# 32u4_denemesi.net
KiCad netlist of a schematic drawn in EAGLE
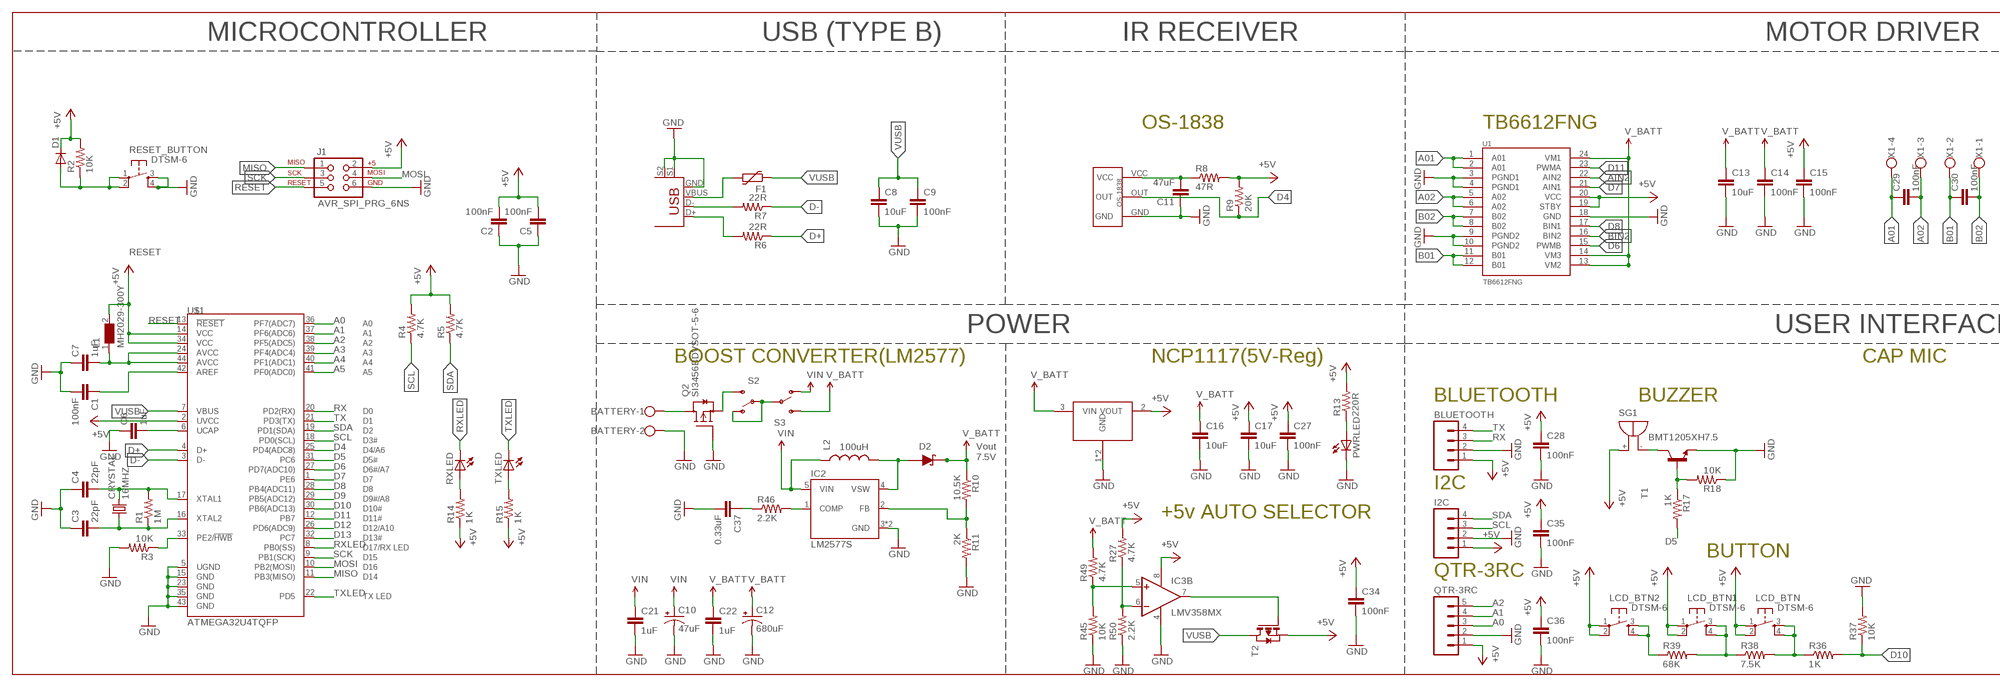
[diagram p0: schematic, sheet 1, part 1 of 2]
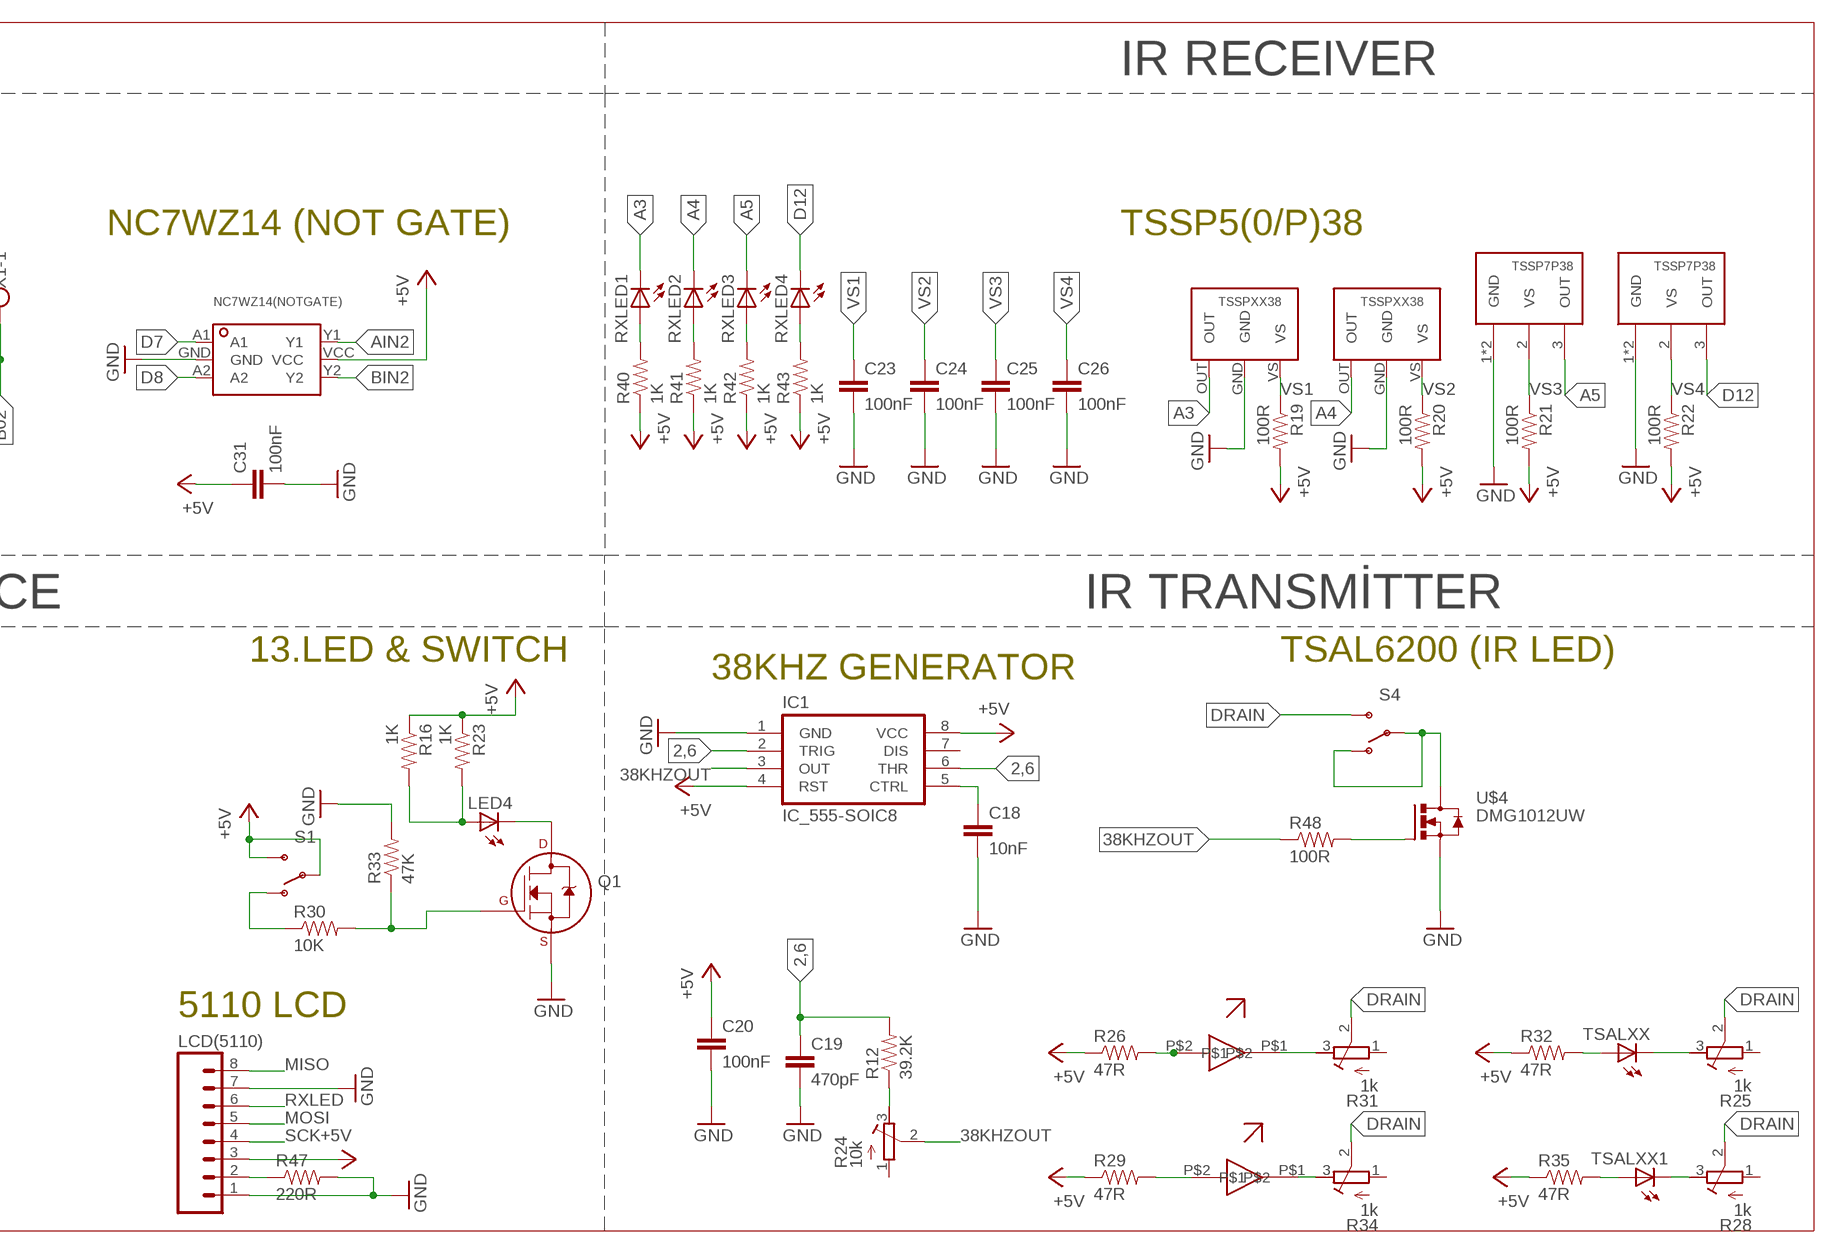
[diagram p1: schematic, sheet 1, part 2 of 2]

(export (version "E")
  (design (tool "Eeschema 10.0.6"))
  (components
    (comp (ref "BATTERY")
      (value "W237-102")
      (footprint "eagle-import:W237-102")
      (fields (field (name "MPN") "237-102"))
      (libsource (lib "eagle-import") (part "W237-102"))
    )
    (comp (ref "BLUETOOTH")
      (value "M04PTH")
      (footprint "eagle-import:1X04")
      (libsource (lib "eagle-import") (part "M04PTH"))
    )
    (comp (ref "C1")
      (value "100nF")
      (footprint "eagle-import:1206")
      (libsource (lib "eagle-import") (part "CAP1206"))
    )
    (comp (ref "C2")
      (value "100nF")
      (footprint "eagle-import:1206")
      (libsource (lib "eagle-import") (part "CAP1206"))
    )
    (comp (ref "C3")
      (value "22pF")
      (footprint "eagle-import:1206")
      (libsource (lib "eagle-import") (part "CAP1206"))
    )
    (comp (ref "C4")
      (value "22pF")
      (footprint "eagle-import:1206")
      (libsource (lib "eagle-import") (part "CAP1206"))
    )
    (comp (ref "C5")
      (value "100nF")
      (footprint "eagle-import:1206")
      (libsource (lib "eagle-import") (part "CAP1206"))
    )
    (comp (ref "C6")
      (value "1uF")
      (footprint "eagle-import:1206")
      (libsource (lib "eagle-import") (part "CAP1206"))
    )
    (comp (ref "C7")
      (value "1uF")
      (footprint "eagle-import:1206")
      (libsource (lib "eagle-import") (part "CAP1206"))
    )
    (comp (ref "C8")
      (value "10uF")
      (footprint "eagle-import:1206")
      (libsource (lib "eagle-import") (part "CAP1206"))
    )
    (comp (ref "C9")
      (value "100nF")
      (footprint "eagle-import:1206")
      (libsource (lib "eagle-import") (part "CAP1206"))
    )
    (comp (ref "C10")
      (value "47uF")
      (footprint "eagle-import:NIPPON_F80")
      (libsource (lib "eagle-import") (part "CAP_POLF80"))
    )
    (comp (ref "C11")
      (value "47uF")
      (footprint "eagle-import:1206")
      (libsource (lib "eagle-import") (part "CAP1206"))
    )
    (comp (ref "C12")
      (value "680uF")
      (footprint "eagle-import:PANASONIC_G")
      (libsource (lib "eagle-import") (part "CAP_POLG"))
    )
    (comp (ref "C13")
      (value "10uF")
      (footprint "eagle-import:1206")
      (libsource (lib "eagle-import") (part "CAP1206"))
    )
    (comp (ref "C14")
      (value "100nF")
      (footprint "eagle-import:1206")
      (libsource (lib "eagle-import") (part "CAP1206"))
    )
    (comp (ref "C15")
      (value "100nF")
      (footprint "eagle-import:1206")
      (libsource (lib "eagle-import") (part "CAP1206"))
    )
    (comp (ref "C16")
      (value "10uF")
      (footprint "eagle-import:1206")
      (libsource (lib "eagle-import") (part "CAP1206"))
    )
    (comp (ref "C17")
      (value "10uF")
      (footprint "eagle-import:1206")
      (libsource (lib "eagle-import") (part "CAP1206"))
    )
    (comp (ref "C18")
      (value "10nF")
      (footprint "eagle-import:1206")
      (libsource (lib "eagle-import") (part "CAP1206"))
    )
    (comp (ref "C19")
      (value "470pF")
      (footprint "eagle-import:1206")
      (libsource (lib "eagle-import") (part "CAP1206"))
    )
    (comp (ref "C20")
      (value "100nF")
      (footprint "eagle-import:1206")
      (libsource (lib "eagle-import") (part "CAP1206"))
    )
    (comp (ref "C21")
      (value "1uF")
      (footprint "eagle-import:1206")
      (libsource (lib "eagle-import") (part "CAP1206"))
    )
    (comp (ref "C22")
      (value "1uF")
      (footprint "eagle-import:1206")
      (libsource (lib "eagle-import") (part "CAP1206"))
    )
    (comp (ref "C23")
      (value "100nF")
      (footprint "eagle-import:1206")
      (libsource (lib "eagle-import") (part "CAP1206"))
    )
    (comp (ref "C24")
      (value "100nF")
      (footprint "eagle-import:1206")
      (libsource (lib "eagle-import") (part "CAP1206"))
    )
    (comp (ref "C25")
      (value "100nF")
      (footprint "eagle-import:1206")
      (libsource (lib "eagle-import") (part "CAP1206"))
    )
    (comp (ref "C26")
      (value "100nF")
      (footprint "eagle-import:1206")
      (libsource (lib "eagle-import") (part "CAP1206"))
    )
    (comp (ref "C27")
      (value "100nF")
      (footprint "eagle-import:1206")
      (libsource (lib "eagle-import") (part "CAP1206"))
    )
    (comp (ref "C28")
      (value "100nF")
      (footprint "eagle-import:1206")
      (libsource (lib "eagle-import") (part "CAP1206"))
    )
    (comp (ref "C29")
      (value "100nF")
      (footprint "eagle-import:1206")
      (libsource (lib "eagle-import") (part "CAP1206"))
    )
    (comp (ref "C30")
      (value "100nF")
      (footprint "eagle-import:1206")
      (libsource (lib "eagle-import") (part "CAP1206"))
    )
    (comp (ref "C31")
      (value "100nF")
      (footprint "eagle-import:1206")
      (libsource (lib "eagle-import") (part "CAP1206"))
    )
    (comp (ref "C34")
      (value "100nF")
      (footprint "eagle-import:1206")
      (libsource (lib "eagle-import") (part "CAP1206"))
    )
    (comp (ref "C35")
      (value "100nF")
      (footprint "eagle-import:1206")
      (libsource (lib "eagle-import") (part "CAP1206"))
    )
    (comp (ref "C36")
      (value "100nF")
      (footprint "eagle-import:1206")
      (libsource (lib "eagle-import") (part "CAP1206"))
    )
    (comp (ref "C37")
      (value "0.33uF")
      (footprint "eagle-import:1206")
      (libsource (lib "eagle-import") (part "CAP1206"))
    )
    (comp (ref "CRYSTAL")
      (value "16MHZ")
      (footprint "eagle-import:CRYSTAL-SMD-5X3")
      (libsource (lib "eagle-import") (part "CRYSTAL5X3"))
    )
    (comp (ref "D1")
      (value "DIODE-MINIMELF")
      (footprint "eagle-import:MINIMELF")
      (libsource (lib "eagle-import") (part "DIODE-MINIMELF"))
    )
    (comp (ref "D2")
      (value "D_SCHOTTKYA")
      (footprint "eagle-import:SMA")
      (libsource (lib "eagle-import") (part "D_SCHOTTKYA"))
    )
    (comp (ref "F1")
      (value "FUSE_PTC-0805")
      (footprint "eagle-import:PTC0805")
      (libsource (lib "eagle-import") (part "FUSE_PTC-0805"))
    )
    (comp (ref "I2C")
      (value "M04PTH")
      (footprint "eagle-import:1X04")
      (libsource (lib "eagle-import") (part "M04PTH"))
    )
    (comp (ref "IC1")
      (value "IC_555-SOIC8")
      (footprint "eagle-import:SOIC-8")
      (libsource (lib "eagle-import") (part "IC_555-SOIC8"))
    )
    (comp (ref "IC2")
      (value "LM2577S")
      (footprint "eagle-import:TO263-5")
      (libsource (lib "eagle-import") (part "LM2577S"))
    )
    (comp (ref "IC3")
      (value "LMV358MX")
      (footprint "eagle-import:SO08")
      (libsource (lib "eagle-import") (part "LMV358?MX"))
    )
    (comp (ref "J1")
      (value "AVR_SPI_PRG_6NS")
      (footprint "eagle-import:2X3-NS")
      (libsource (lib "eagle-import") (part "AVR_SPI_PRG_6NS"))
    )
    (comp (ref "L1")
      (value "MH2029-300Y")
      (footprint "eagle-import:0805")
      (libsource (lib "eagle-import") (part "WE-CBF_0805"))
    )
    (comp (ref "L2")
      (value "INDUCTORPWR")
      (footprint "eagle-import:CDRH125")
      (libsource (lib "eagle-import") (part "INDUCTORPWR"))
    )
    (comp (ref "LCD(5110)")
      (value "M081X08")
      (footprint "eagle-import:1X08")
      (libsource (lib "eagle-import") (part "M081X08"))
    )
    (comp (ref "LCD_BTN")
      (value "DTSM-6")
      (footprint "eagle-import:DTSM-6")
      (libsource (lib "eagle-import") (part "DTSM-6"))
    )
    (comp (ref "LCD_BTN1")
      (value "DTSM-6")
      (footprint "eagle-import:DTSM-6")
      (libsource (lib "eagle-import") (part "DTSM-6"))
    )
    (comp (ref "LCD_BTN2")
      (value "DTSM-6")
      (footprint "eagle-import:DTSM-6")
      (libsource (lib "eagle-import") (part "DTSM-6"))
    )
    (comp (ref "LED4")
      (value "LEDCHIPLED_0805")
      (footprint "eagle-import:CHIPLED_0805")
      (libsource (lib "eagle-import") (part "LEDCHIPLED_0805"))
    )
    (comp (ref "PWRLED")
      (value "LEDCHIPLED_0805")
      (footprint "eagle-import:CHIPLED_0805")
      (libsource (lib "eagle-import") (part "LEDCHIPLED_0805"))
    )
    (comp (ref "Q1")
      (value "2N7000_SOT23")
      (footprint "eagle-import:SOT-23")
      (libsource (lib "eagle-import") (part "2N700_SOT230"))
    )
    (comp (ref "Q2")
      (value "SI3456BDVSOT-5-6")
      (footprint "eagle-import:SOT23-6")
      (libsource (lib "eagle-import") (part "SI3456BDVSOT-5-6"))
    )
    (comp (ref "QTR-3RC")
      (value "M05PTH")
      (footprint "eagle-import:1X05")
      (libsource (lib "eagle-import") (part "M05PTH"))
    )
    (comp (ref "R1")
      (value "1M")
      (footprint "eagle-import:0805")
      (libsource (lib "eagle-import") (part "RESISTOR0805-RES"))
    )
    (comp (ref "R2")
      (value "10K")
      (footprint "eagle-import:0805")
      (libsource (lib "eagle-import") (part "RESISTOR0805-RES"))
    )
    (comp (ref "R3")
      (value "10K")
      (footprint "eagle-import:0805")
      (libsource (lib "eagle-import") (part "RESISTOR0805-RES"))
    )
    (comp (ref "R4")
      (value "4.7K")
      (footprint "eagle-import:0805")
      (libsource (lib "eagle-import") (part "RESISTOR0805-RES"))
    )
    (comp (ref "R5")
      (value "4.7K")
      (footprint "eagle-import:0805")
      (libsource (lib "eagle-import") (part "RESISTOR0805-RES"))
    )
    (comp (ref "R6")
      (value "22R")
      (footprint "eagle-import:0805")
      (libsource (lib "eagle-import") (part "RESISTOR0805-RES"))
    )
    (comp (ref "R7")
      (value "22R")
      (footprint "eagle-import:0805")
      (libsource (lib "eagle-import") (part "RESISTOR0805-RES"))
    )
    (comp (ref "R8")
      (value "47R")
      (footprint "eagle-import:0805")
      (libsource (lib "eagle-import") (part "RESISTOR0805-RES"))
    )
    (comp (ref "R9")
      (value "20K")
      (footprint "eagle-import:0805")
      (libsource (lib "eagle-import") (part "RESISTOR0805-RES"))
    )
    (comp (ref "R10")
      (value "10.5K")
      (footprint "eagle-import:0805")
      (libsource (lib "eagle-import") (part "RESISTOR0805-RES"))
    )
    (comp (ref "R11")
      (value "2K")
      (footprint "eagle-import:0805")
      (libsource (lib "eagle-import") (part "RESISTOR0805-RES"))
    )
    (comp (ref "R12")
      (value "39.2K")
      (footprint "eagle-import:0805")
      (libsource (lib "eagle-import") (part "RESISTOR0805-RES"))
    )
    (comp (ref "R13")
      (value "220R")
      (footprint "eagle-import:0805")
      (libsource (lib "eagle-import") (part "RESISTOR0805-RES"))
    )
    (comp (ref "R14")
      (value "1K")
      (footprint "eagle-import:0805")
      (libsource (lib "eagle-import") (part "RESISTOR0805-RES"))
    )
    (comp (ref "R15")
      (value "1K")
      (footprint "eagle-import:0805")
      (libsource (lib "eagle-import") (part "RESISTOR0805-RES"))
    )
    (comp (ref "R16")
      (value "1K")
      (footprint "eagle-import:0805")
      (libsource (lib "eagle-import") (part "RESISTOR0805-RES"))
    )
    (comp (ref "R17")
      (value "1K")
      (footprint "eagle-import:0805")
      (libsource (lib "eagle-import") (part "RESISTOR0805-RES"))
    )
    (comp (ref "R18")
      (value "10K")
      (footprint "eagle-import:0805")
      (libsource (lib "eagle-import") (part "RESISTOR0805-RES"))
    )
    (comp (ref "R19")
      (value "100R")
      (footprint "eagle-import:0805")
      (libsource (lib "eagle-import") (part "RESISTOR0805-RES"))
    )
    (comp (ref "R20")
      (value "100R")
      (footprint "eagle-import:0805")
      (libsource (lib "eagle-import") (part "RESISTOR0805-RES"))
    )
    (comp (ref "R21")
      (value "100R")
      (footprint "eagle-import:0805")
      (libsource (lib "eagle-import") (part "RESISTOR0805-RES"))
    )
    (comp (ref "R22")
      (value "100R")
      (footprint "eagle-import:0805")
      (libsource (lib "eagle-import") (part "RESISTOR0805-RES"))
    )
    (comp (ref "R23")
      (value "1K")
      (footprint "eagle-import:0805")
      (libsource (lib "eagle-import") (part "RESISTOR0805-RES"))
    )
    (comp (ref "R24")
      (value "10k")
      (footprint "eagle-import:RTRIM3296W")
      (libsource (lib "eagle-import") (part "R-TRIMM3296W"))
    )
    (comp (ref "R25")
      (value "1k")
      (footprint "eagle-import:RTRIM3296W")
      (libsource (lib "eagle-import") (part "R-TRIMM3296W"))
    )
    (comp (ref "R26")
      (value "47R")
      (footprint "eagle-import:0805")
      (libsource (lib "eagle-import") (part "RESISTOR0805-RES"))
    )
    (comp (ref "R27")
      (value "4.7K")
      (footprint "eagle-import:0805")
      (libsource (lib "eagle-import") (part "RESISTOR0805-RES"))
    )
    (comp (ref "R28")
      (value "1k")
      (footprint "eagle-import:RTRIM3296W")
      (libsource (lib "eagle-import") (part "R-TRIMM3296W"))
    )
    (comp (ref "R29")
      (value "47R")
      (footprint "eagle-import:0805")
      (libsource (lib "eagle-import") (part "RESISTOR0805-RES"))
    )
    (comp (ref "R30")
      (value "10K")
      (footprint "eagle-import:0805")
      (libsource (lib "eagle-import") (part "RESISTOR0805-RES"))
    )
    (comp (ref "R31")
      (value "1k")
      (footprint "eagle-import:RTRIM3296W")
      (libsource (lib "eagle-import") (part "R-TRIMM3296W"))
    )
    (comp (ref "R32")
      (value "47R")
      (footprint "eagle-import:0805")
      (libsource (lib "eagle-import") (part "RESISTOR0805-RES"))
    )
    (comp (ref "R33")
      (value "47K")
      (footprint "eagle-import:0805")
      (libsource (lib "eagle-import") (part "RESISTOR0805-RES"))
    )
    (comp (ref "R34")
      (value "1k")
      (footprint "eagle-import:RTRIM3296W")
      (libsource (lib "eagle-import") (part "R-TRIMM3296W"))
    )
    (comp (ref "R35")
      (value "47R")
      (footprint "eagle-import:0805")
      (libsource (lib "eagle-import") (part "RESISTOR0805-RES"))
    )
    (comp (ref "R36")
      (value "1K")
      (footprint "eagle-import:0805")
      (libsource (lib "eagle-import") (part "RESISTOR0805-RES"))
    )
    (comp (ref "R37")
      (value "10K")
      (footprint "eagle-import:0805")
      (libsource (lib "eagle-import") (part "RESISTOR0805-RES"))
    )
    (comp (ref "R38")
      (value "7.5K")
      (footprint "eagle-import:0805")
      (libsource (lib "eagle-import") (part "RESISTOR0805-RES"))
    )
    (comp (ref "R39")
      (value "68K")
      (footprint "eagle-import:0805")
      (libsource (lib "eagle-import") (part "RESISTOR0805-RES"))
    )
    (comp (ref "R40")
      (value "1K")
      (footprint "eagle-import:0805")
      (libsource (lib "eagle-import") (part "RESISTOR0805-RES"))
    )
    (comp (ref "R41")
      (value "1K")
      (footprint "eagle-import:0805")
      (libsource (lib "eagle-import") (part "RESISTOR0805-RES"))
    )
    (comp (ref "R42")
      (value "1K")
      (footprint "eagle-import:0805")
      (libsource (lib "eagle-import") (part "RESISTOR0805-RES"))
    )
    (comp (ref "R43")
      (value "1K")
      (footprint "eagle-import:0805")
      (libsource (lib "eagle-import") (part "RESISTOR0805-RES"))
    )
    (comp (ref "R45")
      (value "10K")
      (footprint "eagle-import:0805")
      (libsource (lib "eagle-import") (part "RESISTOR0805-RES"))
    )
    (comp (ref "R46")
      (value "2.2K")
      (footprint "eagle-import:0805")
      (libsource (lib "eagle-import") (part "RESISTOR0805-RES"))
    )
    (comp (ref "R47")
      (value "220R")
      (footprint "eagle-import:0805")
      (libsource (lib "eagle-import") (part "RESISTOR0805-RES"))
    )
    (comp (ref "R48")
      (value "100R")
      (footprint "eagle-import:0805")
      (libsource (lib "eagle-import") (part "RESISTOR0805-RES"))
    )
    (comp (ref "R49")
      (value "4.7K")
      (footprint "eagle-import:0805")
      (libsource (lib "eagle-import") (part "RESISTOR0805-RES"))
    )
    (comp (ref "R50")
      (value "2.2K")
      (footprint "eagle-import:0805")
      (libsource (lib "eagle-import") (part "RESISTOR0805-RES"))
    )
    (comp (ref "RESET_BUTTON")
      (value "DTSM-6")
      (footprint "eagle-import:DTSM-6")
      (libsource (lib "eagle-import") (part "DTSM-6"))
    )
    (comp (ref "RXLED")
      (value "LEDCHIPLED_0805")
      (footprint "eagle-import:CHIPLED_0805")
      (libsource (lib "eagle-import") (part "LEDCHIPLED_0805"))
    )
    (comp (ref "RXLED1")
      (value "LEDCHIPLED_0805")
      (footprint "eagle-import:CHIPLED_0805")
      (libsource (lib "eagle-import") (part "LEDCHIPLED_0805"))
    )
    (comp (ref "RXLED2")
      (value "LEDCHIPLED_0805")
      (footprint "eagle-import:CHIPLED_0805")
      (libsource (lib "eagle-import") (part "LEDCHIPLED_0805"))
    )
    (comp (ref "RXLED3")
      (value "LEDCHIPLED_0805")
      (footprint "eagle-import:CHIPLED_0805")
      (libsource (lib "eagle-import") (part "LEDCHIPLED_0805"))
    )
    (comp (ref "RXLED4")
      (value "LEDCHIPLED_0805")
      (footprint "eagle-import:CHIPLED_0805")
      (libsource (lib "eagle-import") (part "LEDCHIPLED_0805"))
    )
    (comp (ref "S1")
      (value "SWITCH-SPDTPTH")
      (footprint "eagle-import:SWITCH-SPDT")
      (libsource (lib "eagle-import") (part "SWITCH-SPDTPTH"))
    )
    (comp (ref "S2")
      (value "SWITCH-SPDTPTH")
      (footprint "eagle-import:SWITCH-SPDT")
      (libsource (lib "eagle-import") (part "SWITCH-SPDTPTH"))
    )
    (comp (ref "S3")
      (value "SWITCH-SPDTPTH")
      (footprint "eagle-import:SWITCH-SPDT")
      (libsource (lib "eagle-import") (part "SWITCH-SPDTPTH"))
    )
    (comp (ref "S4")
      (value "SWITCH-SPDTPTH")
      (footprint "eagle-import:SWITCH-SPDT")
      (libsource (lib "eagle-import") (part "SWITCH-SPDTPTH"))
    )
    (comp (ref "SG1")
      (value "BMT1205XH7.5")
      (footprint "eagle-import:BMT1205XH7.5")
      (libsource (lib "eagle-import") (part "BMT1205XH7.5"))
    )
    (comp (ref "T1")
      (value "MMBT2222ALT1-NPN-SOT23-BEC")
      (footprint "eagle-import:SOT23-BEC")
      (libsource (lib "eagle-import") (part "-NPN-SOT23-BECMMBT2222ALT1"))
    )
    (comp (ref "T2")
      (value "PMOSSOT23")
      (footprint "eagle-import:SOT-23")
      (libsource (lib "eagle-import") (part "PMOSSOT23"))
    )
    (comp (ref "TSALXX")
      (value "LED5MM")
      (footprint "eagle-import:LED5MM")
      (libsource (lib "eagle-import") (part "LED5MM"))
    )
    (comp (ref "TSALXX1")
      (value "LED5MM")
      (footprint "eagle-import:LED5MM")
      (libsource (lib "eagle-import") (part "LED5MM"))
    )
    (comp (ref "TXLED")
      (value "LEDCHIPLED_0805")
      (footprint "eagle-import:CHIPLED_0805")
      (libsource (lib "eagle-import") (part "LEDCHIPLED_0805"))
    )
    (comp (ref "U$1")
      (value "ATMEGA32U4TQFP")
      (footprint "eagle-import:SPARKFUN-DIGITALIC_TQFP44")
      (libsource (lib "eagle-import") (part "ATMEGA32U4TQFP"))
    )
    (comp (ref "U$2")
      (value "USB+SHIELD")
      (footprint "eagle-import:USB-B-PTH")
      (libsource (lib "eagle-import") (part "USB+SHIELD"))
    )
    (comp (ref "U$3")
      (value "OS-1838")
      (footprint "eagle-import:OS-1838")
      (libsource (lib "eagle-import") (part "OS-1838"))
    )
    (comp (ref "U$4")
      (value "DMG1012UW")
      (footprint "eagle-import:SOT323")
      (libsource (lib "eagle-import") (part "DMG1012UW"))
    )
    (comp (ref "U$5")
      (value "NCP1117")
      (footprint "eagle-import:SOT223")
      (libsource (lib "eagle-import") (part "NCP1117"))
    )
    (comp (ref "U$6")
      (value "TSSP7P38")
      (footprint "eagle-import:TSSP7P38")
      (libsource (lib "eagle-import") (part "TSSP7P38"))
    )
    (comp (ref "U$7")
      (value "TSSP7P38")
      (footprint "eagle-import:TSSP7P38")
      (libsource (lib "eagle-import") (part "TSSP7P38"))
    )
    (comp (ref "U$8")
      (value "TSSPXX38")
      (footprint "eagle-import:TSSPXX38")
      (libsource (lib "eagle-import") (part "TSSPXX38"))
    )
    (comp (ref "U$9")
      (value "TSSPXX38")
      (footprint "eagle-import:TSSPXX38")
      (libsource (lib "eagle-import") (part "TSSPXX38"))
    )
    (comp (ref "U$10")
      (value "NC7WZ14(NOTGATE)")
      (footprint "eagle-import:SC-70-6")
      (libsource (lib "eagle-import") (part "NC7WZ14(NOTGATE)"))
    )
    (comp (ref "U$11")
      (value "IRLED")
      (footprint "eagle-import:IRLED")
      (libsource (lib "eagle-import") (part "IRLED"))
    )
    (comp (ref "U$12")
      (value "IRLED")
      (footprint "eagle-import:IRLED")
      (libsource (lib "eagle-import") (part "IRLED"))
    )
    (comp (ref "U1")
      (value "TB6612FNG")
      (footprint "eagle-import:SSOP24")
      (libsource (lib "eagle-import") (part "TB6621FNG"))
    )
    (comp (ref "X1")
      (value "W237-4")
      (footprint "eagle-import:W237-4")
      (libsource (lib "eagle-import") (part "W237-4"))
    )
  )
  (nets
    (net (code "1") (name "+5V") (class "Default")
      (node (ref "BLUETOOTH") (pin "1") (pinfunction "1_1") (pintype "passive"))
      (node (ref "C15") (pin "1") (pinfunction "1_1") (pintype "passive"))
      (node (ref "C17") (pin "1") (pinfunction "1_1") (pintype "passive"))
      (node (ref "C2") (pin "2") (pinfunction "2_2") (pintype "passive"))
      (node (ref "C20") (pin "1") (pinfunction "1_1") (pintype "passive"))
      (node (ref "C27") (pin "1") (pinfunction "1_1") (pintype "passive"))
      (node (ref "C28") (pin "1") (pinfunction "1_1") (pintype "passive"))
      (node (ref "C31") (pin "1") (pinfunction "1_1") (pintype "passive"))
      (node (ref "C34") (pin "1") (pinfunction "1_1") (pintype "passive"))
      (node (ref "C35") (pin "1") (pinfunction "1_1") (pintype "passive"))
      (node (ref "C36") (pin "1") (pinfunction "1_1") (pintype "passive"))
      (node (ref "C5") (pin "2") (pinfunction "2_2") (pintype "passive"))
      (node (ref "D1") (pin "C") (pinfunction "C_C") (pintype "passive"))
      (node (ref "I2C") (pin "1") (pinfunction "1_1") (pintype "passive"))
      (node (ref "IC1") (pin "4") (pinfunction "RST_4") (pintype "input"))
      (node (ref "IC1") (pin "8") (pinfunction "VCC_8") (pintype "power_in"))
      (node (ref "IC3") (pin "8") (pinfunction "V+_8") (pintype "power_in"))
      (node (ref "J1") (pin "2") (pinfunction "2_2") (pintype "passive"))
      (node (ref "L1") (pin "2") (pinfunction "2_2") (pintype "passive"))
      (node (ref "LCD(5110)") (pin "3") (pinfunction "3_3") (pintype "passive"))
      (node (ref "LCD_BTN") (pin "1") (pinfunction "1_1") (pintype "passive"))
      (node (ref "LCD_BTN") (pin "2") (pinfunction "2_2") (pintype "passive"))
      (node (ref "LCD_BTN1") (pin "1") (pinfunction "1_1") (pintype "passive"))
      (node (ref "LCD_BTN1") (pin "2") (pinfunction "2_2") (pintype "passive"))
      (node (ref "LCD_BTN2") (pin "1") (pinfunction "1_1") (pintype "passive"))
      (node (ref "LCD_BTN2") (pin "2") (pinfunction "2_2") (pintype "passive"))
      (node (ref "QTR-3RC") (pin "1") (pinfunction "1_1") (pintype "passive"))
      (node (ref "R13") (pin "2") (pinfunction "2_2") (pintype "passive"))
      (node (ref "R14") (pin "1") (pinfunction "1_1") (pintype "passive"))
      (node (ref "R15") (pin "1") (pinfunction "1_1") (pintype "passive"))
      (node (ref "R16") (pin "1") (pinfunction "1_1") (pintype "passive"))
      (node (ref "R19") (pin "2") (pinfunction "2_2") (pintype "passive"))
      (node (ref "R2") (pin "2") (pinfunction "2_2") (pintype "passive"))
      (node (ref "R20") (pin "2") (pinfunction "2_2") (pintype "passive"))
      (node (ref "R21") (pin "2") (pinfunction "2_2") (pintype "passive"))
      (node (ref "R22") (pin "2") (pinfunction "2_2") (pintype "passive"))
      (node (ref "R23") (pin "1") (pinfunction "1_1") (pintype "passive"))
      (node (ref "R26") (pin "1") (pinfunction "1_1") (pintype "passive"))
      (node (ref "R27") (pin "2") (pinfunction "2_2") (pintype "passive"))
      (node (ref "R29") (pin "1") (pinfunction "1_1") (pintype "passive"))
      (node (ref "R32") (pin "1") (pinfunction "1_1") (pintype "passive"))
      (node (ref "R35") (pin "1") (pinfunction "1_1") (pintype "passive"))
      (node (ref "R4") (pin "2") (pinfunction "2_2") (pintype "passive"))
      (node (ref "R40") (pin "1") (pinfunction "1_1") (pintype "passive"))
      (node (ref "R41") (pin "1") (pinfunction "1_1") (pintype "passive"))
      (node (ref "R42") (pin "1") (pinfunction "1_1") (pintype "passive"))
      (node (ref "R43") (pin "1") (pinfunction "1_1") (pintype "passive"))
      (node (ref "R5") (pin "2") (pinfunction "2_2") (pintype "passive"))
      (node (ref "R8") (pin "2") (pinfunction "2_2") (pintype "passive"))
      (node (ref "R9") (pin "2") (pinfunction "2_2") (pintype "passive"))
      (node (ref "S1") (pin "2") (pinfunction "P_2") (pintype "passive"))
      (node (ref "S1") (pin "3") (pinfunction "S_3") (pintype "passive"))
      (node (ref "SG1") (pin "+") (pinfunction "+_+") (pintype "passive"))
      (node (ref "T2") (pin "2") (pinfunction "S_2") (pintype "passive"))
      (node (ref "U$1") (pin "14") (pinfunction "VCC_14") (pintype "bidirectional"))
      (node (ref "U$1") (pin "2") (pinfunction "UVCC_2") (pintype "bidirectional"))
      (node (ref "U$1") (pin "34") (pinfunction "VCC_34") (pintype "bidirectional"))
      (node (ref "U$10") (pin "VCC") (pinfunction "VCC_VCC") (pintype "bidirectional"))
      (node (ref "U$5") (pin "2") (pinfunction "VOUT_2") (pintype "bidirectional"))
      (node (ref "U1") (pin "19") (pinfunction "STBY_19") (pintype "bidirectional"))
      (node (ref "U1") (pin "20") (pinfunction "VCC_20") (pintype "bidirectional"))
    )
    (net (code "2") (name "/A0") (class "Default")
      (node (ref "QTR-3RC") (pin "3") (pinfunction "3_3") (pintype "passive"))
      (node (ref "U$1") (pin "36") (pinfunction "PF7(ADC7)_36") (pintype "bidirectional"))
    )
    (net (code "3") (name "/A1") (class "Default")
      (node (ref "QTR-3RC") (pin "4") (pinfunction "4_4") (pintype "passive"))
      (node (ref "U$1") (pin "37") (pinfunction "PF6(ADC6)_37") (pintype "bidirectional"))
    )
    (net (code "4") (name "/A2") (class "Default")
      (node (ref "QTR-3RC") (pin "5") (pinfunction "5_5") (pintype "passive"))
      (node (ref "U$1") (pin "38") (pinfunction "PF5(ADC5)_38") (pintype "bidirectional"))
    )
    (net (code "5") (name "/D5") (class "Default")
      (node (ref "R17") (pin "2") (pinfunction "2_2") (pintype "passive"))
      (node (ref "U$1") (pin "31") (pinfunction "PC6_31") (pintype "bidirectional"))
    )
    (net (code "6") (name "/D9") (class "Default")
      (node (ref "U$1") (pin "29") (pinfunction "PB5(ADC12)_29") (pintype "bidirectional"))
    )
    (net (code "7") (name "/D13") (class "Default")
      (node (ref "U$1") (pin "32") (pinfunction "PC7_32") (pintype "bidirectional"))
    )
    (net (code "8") (name "/MOSI") (class "Default")
      (node (ref "J1") (pin "4") (pinfunction "4_4") (pintype "passive"))
      (node (ref "LCD(5110)") (pin "5") (pinfunction "5_5") (pintype "passive"))
      (node (ref "U$1") (pin "10") (pinfunction "PB2(MOSI)_10") (pintype "bidirectional"))
    )
    (net (code "9") (name "/RX") (class "Default")
      (node (ref "BLUETOOTH") (pin "3") (pinfunction "3_3") (pintype "passive"))
      (node (ref "U$1") (pin "20") (pinfunction "PD2(RX)_20") (pintype "bidirectional"))
    )
    (net (code "10") (name "/TX") (class "Default")
      (node (ref "BLUETOOTH") (pin "4") (pinfunction "4_4") (pintype "passive"))
      (node (ref "U$1") (pin "21") (pinfunction "PD3(TX)_21") (pintype "bidirectional"))
    )
    (net (code "11") (name "2,6") (class "Default")
      (node (ref "C19") (pin "1") (pinfunction "1_1") (pintype "passive"))
      (node (ref "IC1") (pin "2") (pinfunction "TRIG_2") (pintype "input"))
      (node (ref "IC1") (pin "6") (pinfunction "THR_6") (pintype "input"))
      (node (ref "R12") (pin "2") (pinfunction "2_2") (pintype "passive"))
    )
    (net (code "12") (name "38KHZOUT") (class "Default")
      (node (ref "IC1") (pin "3") (pinfunction "OUT_3") (pintype "output"))
      (node (ref "R24") (pin "2") (pinfunction "S_2") (pintype "passive"))
      (node (ref "R48") (pin "1") (pinfunction "1_1") (pintype "passive"))
    )
    (net (code "13") (name "A01") (class "Default")
      (node (ref "C29") (pin "1") (pinfunction "1_1") (pintype "passive"))
      (node (ref "U1") (pin "1") (pinfunction "A01_1") (pintype "bidirectional"))
      (node (ref "U1") (pin "2") (pinfunction "A01_2") (pintype "bidirectional"))
      (node (ref "X1") (pin "4") (pinfunction "KL_4") (pintype "passive"))
    )
    (net (code "14") (name "A02") (class "Default")
      (node (ref "C29") (pin "2") (pinfunction "2_2") (pintype "passive"))
      (node (ref "U1") (pin "5") (pinfunction "A02_5") (pintype "bidirectional"))
      (node (ref "U1") (pin "6") (pinfunction "A02_6") (pintype "bidirectional"))
      (node (ref "X1") (pin "3") (pinfunction "KL_3") (pintype "passive"))
    )
    (net (code "15") (name "A3") (class "Default")
      (node (ref "RXLED1") (pin "C") (pinfunction "C_C") (pintype "passive"))
      (node (ref "U$1") (pin "39") (pinfunction "PF4(ADC4)_39") (pintype "bidirectional"))
      (node (ref "U$9") (pin "OUT") (pinfunction "OUT_OUT") (pintype "bidirectional"))
    )
    (net (code "16") (name "A4") (class "Default")
      (node (ref "RXLED2") (pin "C") (pinfunction "C_C") (pintype "passive"))
      (node (ref "U$1") (pin "40") (pinfunction "PF1(ADC1)_40") (pintype "bidirectional"))
      (node (ref "U$8") (pin "OUT") (pinfunction "OUT_OUT") (pintype "bidirectional"))
    )
    (net (code "17") (name "A5") (class "Default")
      (node (ref "RXLED3") (pin "C") (pinfunction "C_C") (pintype "passive"))
      (node (ref "U$1") (pin "41") (pinfunction "PF0(ADC0)_41") (pintype "bidirectional"))
      (node (ref "U$6") (pin "3") (pinfunction "OUT_3") (pintype "bidirectional"))
    )
    (net (code "18") (name "AIN2") (class "Default")
      (node (ref "U$10") (pin "Y1") (pinfunction "Y1_Y1") (pintype "bidirectional"))
      (node (ref "U1") (pin "22") (pinfunction "AIN2_22") (pintype "bidirectional"))
    )
    (net (code "19") (name "B01") (class "Default")
      (node (ref "C30") (pin "1") (pinfunction "1_1") (pintype "passive"))
      (node (ref "U1") (pin "11") (pinfunction "B01_11") (pintype "bidirectional"))
      (node (ref "U1") (pin "12") (pinfunction "B01_12") (pintype "bidirectional"))
      (node (ref "X1") (pin "2") (pinfunction "KL_2") (pintype "passive"))
    )
    (net (code "20") (name "B02") (class "Default")
      (node (ref "C30") (pin "2") (pinfunction "2_2") (pintype "passive"))
      (node (ref "U1") (pin "7") (pinfunction "B02_7") (pintype "bidirectional"))
      (node (ref "U1") (pin "8") (pinfunction "B02_8") (pintype "bidirectional"))
      (node (ref "X1") (pin "1") (pinfunction "KL_1") (pintype "passive"))
    )
    (net (code "21") (name "BIN2") (class "Default")
      (node (ref "U$10") (pin "Y2") (pinfunction "Y2_Y2") (pintype "bidirectional"))
      (node (ref "U1") (pin "16") (pinfunction "BIN2_16") (pintype "bidirectional"))
    )
    (net (code "22") (name "D+") (class "Default")
      (node (ref "R6") (pin "1") (pinfunction "1_1") (pintype "passive"))
      (node (ref "U$1") (pin "4") (pinfunction "D+_4") (pintype "bidirectional"))
    )
    (net (code "23") (name "D-") (class "Default")
      (node (ref "R7") (pin "1") (pinfunction "1_1") (pintype "passive"))
      (node (ref "U$1") (pin "3") (pinfunction "D-_3") (pintype "bidirectional"))
    )
    (net (code "24") (name "D4") (class "Default")
      (node (ref "R9") (pin "1") (pinfunction "1_1") (pintype "passive"))
      (node (ref "U$1") (pin "25") (pinfunction "PD4(ADC8)_25") (pintype "bidirectional"))
      (node (ref "U$3") (pin "OUT") (pinfunction "OUT_OUT") (pintype "bidirectional"))
    )
    (net (code "25") (name "D6") (class "Default")
      (node (ref "U$1") (pin "27") (pinfunction "PD7(ADC10)_27") (pintype "bidirectional"))
      (node (ref "U1") (pin "15") (pinfunction "PWMB_15") (pintype "bidirectional"))
    )
    (net (code "26") (name "D7") (class "Default")
      (node (ref "U$1") (pin "1") (pinfunction "PE6_1") (pintype "bidirectional"))
      (node (ref "U$10") (pin "A1") (pinfunction "A1_A1") (pintype "bidirectional"))
      (node (ref "U1") (pin "21") (pinfunction "AIN1_21") (pintype "bidirectional"))
    )
    (net (code "27") (name "D8") (class "Default")
      (node (ref "U$1") (pin "28") (pinfunction "PB4(ADC11)_28") (pintype "bidirectional"))
      (node (ref "U$10") (pin "A2") (pinfunction "A2_A2") (pintype "bidirectional"))
      (node (ref "U1") (pin "17") (pinfunction "BIN1_17") (pintype "bidirectional"))
    )
    (net (code "28") (name "D10") (class "Default")
      (node (ref "R36") (pin "2") (pinfunction "2_2") (pintype "passive"))
      (node (ref "R37") (pin "1") (pinfunction "1_1") (pintype "passive"))
      (node (ref "U$1") (pin "30") (pinfunction "PB6(ADC13)_30") (pintype "bidirectional"))
    )
    (net (code "29") (name "D11") (class "Default")
      (node (ref "U$1") (pin "12") (pinfunction "PB7_12") (pintype "bidirectional"))
      (node (ref "U1") (pin "23") (pinfunction "PWMA_23") (pintype "bidirectional"))
    )
    (net (code "30") (name "D12") (class "Default")
      (node (ref "RXLED4") (pin "C") (pinfunction "C_C") (pintype "passive"))
      (node (ref "U$1") (pin "26") (pinfunction "PD6(ADC9)_26") (pintype "bidirectional"))
      (node (ref "U$7") (pin "3") (pinfunction "OUT_3") (pintype "bidirectional"))
    )
    (net (code "31") (name "DRAIN") (class "Default")
      (node (ref "R25") (pin "2") (pinfunction "S_2") (pintype "passive"))
      (node (ref "R28") (pin "2") (pinfunction "S_2") (pintype "passive"))
      (node (ref "R31") (pin "2") (pinfunction "S_2") (pintype "passive"))
      (node (ref "R34") (pin "2") (pinfunction "S_2") (pintype "passive"))
      (node (ref "S4") (pin "3") (pinfunction "S_3") (pintype "passive"))
    )
    (net (code "32") (name "GND") (class "Default")
      (node (ref "BATTERY") (pin "2") (pinfunction "KL_2") (pintype "passive"))
      (node (ref "BLUETOOTH") (pin "2") (pinfunction "2_2") (pintype "passive"))
      (node (ref "C1") (pin "2") (pinfunction "2_2") (pintype "passive"))
      (node (ref "C10") (pin "-") (pinfunction "-_-") (pintype "passive"))
      (node (ref "C11") (pin "1") (pinfunction "1_1") (pintype "passive"))
      (node (ref "C12") (pin "-") (pinfunction "-_-") (pintype "passive"))
      (node (ref "C13") (pin "2") (pinfunction "2_2") (pintype "passive"))
      (node (ref "C14") (pin "2") (pinfunction "2_2") (pintype "passive"))
      (node (ref "C15") (pin "2") (pinfunction "2_2") (pintype "passive"))
      (node (ref "C16") (pin "2") (pinfunction "2_2") (pintype "passive"))
      (node (ref "C17") (pin "2") (pinfunction "2_2") (pintype "passive"))
      (node (ref "C18") (pin "2") (pinfunction "2_2") (pintype "passive"))
      (node (ref "C19") (pin "2") (pinfunction "2_2") (pintype "passive"))
      (node (ref "C2") (pin "1") (pinfunction "1_1") (pintype "passive"))
      (node (ref "C20") (pin "2") (pinfunction "2_2") (pintype "passive"))
      (node (ref "C21") (pin "2") (pinfunction "2_2") (pintype "passive"))
      (node (ref "C22") (pin "2") (pinfunction "2_2") (pintype "passive"))
      (node (ref "C23") (pin "2") (pinfunction "2_2") (pintype "passive"))
      (node (ref "C24") (pin "2") (pinfunction "2_2") (pintype "passive"))
      (node (ref "C25") (pin "2") (pinfunction "2_2") (pintype "passive"))
      (node (ref "C26") (pin "2") (pinfunction "2_2") (pintype "passive"))
      (node (ref "C27") (pin "2") (pinfunction "2_2") (pintype "passive"))
      (node (ref "C28") (pin "2") (pinfunction "2_2") (pintype "passive"))
      (node (ref "C3") (pin "1") (pinfunction "1_1") (pintype "passive"))
      (node (ref "C31") (pin "2") (pinfunction "2_2") (pintype "passive"))
      (node (ref "C34") (pin "2") (pinfunction "2_2") (pintype "passive"))
      (node (ref "C35") (pin "2") (pinfunction "2_2") (pintype "passive"))
      (node (ref "C36") (pin "2") (pinfunction "2_2") (pintype "passive"))
      (node (ref "C37") (pin "2") (pinfunction "2_2") (pintype "passive"))
      (node (ref "C4") (pin "1") (pinfunction "1_1") (pintype "passive"))
      (node (ref "C5") (pin "1") (pinfunction "1_1") (pintype "passive"))
      (node (ref "C6") (pin "1") (pinfunction "1_1") (pintype "passive"))
      (node (ref "C7") (pin "1") (pinfunction "1_1") (pintype "passive"))
      (node (ref "C8") (pin "2") (pinfunction "2_2") (pintype "passive"))
      (node (ref "C9") (pin "2") (pinfunction "2_2") (pintype "passive"))
      (node (ref "I2C") (pin "2") (pinfunction "2_2") (pintype "passive"))
      (node (ref "IC1") (pin "1") (pinfunction "GND_1") (pintype "power_in"))
      (node (ref "IC2") (pin "3") (pinfunction "GND_3") (pintype "power_in"))
      (node (ref "IC2") (pin "6") (pinfunction "GND_6") (pintype "power_in"))
      (node (ref "IC3") (pin "4") (pinfunction "V-_4") (pintype "power_in"))
      (node (ref "J1") (pin "6") (pinfunction "6_6") (pintype "passive"))
      (node (ref "LCD(5110)") (pin "1") (pinfunction "1_1") (pintype "passive"))
      (node (ref "LCD(5110)") (pin "7") (pinfunction "7_7") (pintype "passive"))
      (node (ref "PWRLED") (pin "C") (pinfunction "C_C") (pintype "passive"))
      (node (ref "Q1") (pin "2") (pinfunction "S_2") (pintype "bidirectional"))
      (node (ref "Q2") (pin "3") (pinfunction "G_3") (pintype "passive"))
      (node (ref "QTR-3RC") (pin "2") (pinfunction "2_2") (pintype "passive"))
      (node (ref "R11") (pin "2") (pinfunction "2_2") (pintype "passive"))
      (node (ref "R18") (pin "1") (pinfunction "1_1") (pintype "passive"))
      (node (ref "R3") (pin "2") (pinfunction "2_2") (pintype "passive"))
      (node (ref "R33") (pin "2") (pinfunction "2_2") (pintype "passive"))
      (node (ref "R37") (pin "2") (pinfunction "2_2") (pintype "passive"))
      (node (ref "R45") (pin "1") (pinfunction "1_1") (pintype "passive"))
      (node (ref "R47") (pin "2") (pinfunction "2_2") (pintype "passive"))
      (node (ref "R50") (pin "1") (pinfunction "1_1") (pintype "passive"))
      (node (ref "RESET_BUTTON") (pin "3") (pinfunction "3_3") (pintype "passive"))
      (node (ref "RESET_BUTTON") (pin "4") (pinfunction "4_4") (pintype "passive"))
      (node (ref "T1") (pin "E") (pinfunction "E_E") (pintype "passive"))
      (node (ref "U$1") (pin "15") (pinfunction "GND_15") (pintype "bidirectional"))
      (node (ref "U$1") (pin "23") (pinfunction "GND_23") (pintype "bidirectional"))
      (node (ref "U$1") (pin "35") (pinfunction "GND_35") (pintype "bidirectional"))
      (node (ref "U$1") (pin "43") (pinfunction "GND_43") (pintype "bidirectional"))
      (node (ref "U$1") (pin "5") (pinfunction "UGND_5") (pintype "bidirectional"))
      (node (ref "U$10") (pin "GND") (pinfunction "GND_GND") (pintype "bidirectional"))
      (node (ref "U$2") (pin "GND") (pinfunction "GND_GND") (pintype "bidirectional"))
      (node (ref "U$2") (pin "S1") (pinfunction "S1_S1") (pintype "bidirectional"))
      (node (ref "U$2") (pin "S2") (pinfunction "S2_S2") (pintype "bidirectional"))
      (node (ref "U$3") (pin "GND") (pinfunction "GND_GND") (pintype "bidirectional"))
      (node (ref "U$4") (pin "2") (pinfunction "S_2") (pintype "passive"))
      (node (ref "U$5") (pin "1") (pinfunction "GND_1") (pintype "bidirectional"))
      (node (ref "U$5") (pin "4") (pinfunction "GND_4") (pintype "bidirectional"))
      (node (ref "U$6") (pin "1") (pinfunction "GND_1") (pintype "bidirectional"))
      (node (ref "U$6") (pin "4") (pinfunction "GND_4") (pintype "bidirectional"))
      (node (ref "U$7") (pin "1") (pinfunction "GND_1") (pintype "bidirectional"))
      (node (ref "U$7") (pin "4") (pinfunction "GND_4") (pintype "bidirectional"))
      (node (ref "U$8") (pin "GND") (pinfunction "GND_GND") (pintype "bidirectional"))
      (node (ref "U$9") (pin "GND") (pinfunction "GND_GND") (pintype "bidirectional"))
      (node (ref "U1") (pin "10") (pinfunction "PGND2_10") (pintype "bidirectional"))
      (node (ref "U1") (pin "18") (pinfunction "GND_18") (pintype "bidirectional"))
      (node (ref "U1") (pin "3") (pinfunction "PGND1_3") (pintype "bidirectional"))
      (node (ref "U1") (pin "4") (pinfunction "PGND1_4") (pintype "bidirectional"))
      (node (ref "U1") (pin "9") (pinfunction "PGND2_9") (pintype "bidirectional"))
    )
    (net (code "33") (name "MISO") (class "Default")
      (node (ref "J1") (pin "1") (pinfunction "1_1") (pintype "passive"))
      (node (ref "LCD(5110)") (pin "8") (pinfunction "8_8") (pintype "passive"))
      (node (ref "U$1") (pin "11") (pinfunction "PB3(MISO)_11") (pintype "bidirectional"))
    )
    (net (code "34") (name "Net-(BATTERYA-KL)") (class "Default")
      (node (ref "BATTERY") (pin "1") (pinfunction "KL_1") (pintype "passive"))
      (node (ref "Q2") (pin "1") (pinfunction "D_1") (pintype "passive"))
      (node (ref "Q2") (pin "2") (pinfunction "D_2") (pintype "passive"))
      (node (ref "Q2") (pin "5") (pinfunction "D_5") (pintype "passive"))
      (node (ref "Q2") (pin "6") (pinfunction "D_6") (pintype "passive"))
    )
    (net (code "35") (name "Net-(C7-Pad2)") (class "Default")
      (node (ref "C7") (pin "2") (pinfunction "2_2") (pintype "passive"))
      (node (ref "L1") (pin "1") (pinfunction "1_1") (pintype "passive"))
      (node (ref "U$1") (pin "24") (pinfunction "AVCC_24") (pintype "bidirectional"))
      (node (ref "U$1") (pin "44") (pinfunction "AVCC_44") (pintype "bidirectional"))
    )
    (net (code "36") (name "Net-(C11-Pad2)") (class "Default")
      (node (ref "C11") (pin "2") (pinfunction "2_2") (pintype "passive"))
      (node (ref "R8") (pin "1") (pinfunction "1_1") (pintype "passive"))
      (node (ref "U$3") (pin "VCC") (pinfunction "VCC_VCC") (pintype "bidirectional"))
    )
    (net (code "37") (name "Net-(C37-Pad1)") (class "Default")
      (node (ref "C37") (pin "1") (pinfunction "1_1") (pintype "passive"))
      (node (ref "R46") (pin "1") (pinfunction "1_1") (pintype "passive"))
    )
    (net (code "38") (name "Net-(CRYSTAL-2)") (class "Default")
      (node (ref "C4") (pin "2") (pinfunction "2_2") (pintype "passive"))
      (node (ref "CRYSTAL") (pin "3") (pinfunction "2_3") (pintype "passive"))
      (node (ref "R1") (pin "2") (pinfunction "2_2") (pintype "passive"))
      (node (ref "U$1") (pin "17") (pinfunction "XTAL1_17") (pintype "bidirectional"))
    )
    (net (code "39") (name "Net-(D2-A)") (class "Default")
      (node (ref "D2") (pin "2") (pinfunction "A_2") (pintype "passive"))
      (node (ref "IC2") (pin "4") (pinfunction "VSW_4") (pintype "bidirectional"))
      (node (ref "L2") (pin "2") (pinfunction "2_2") (pintype "passive"))
    )
    (net (code "40") (name "Net-(F1-Pad2)") (class "Default")
      (node (ref "F1") (pin "2") (pinfunction "2_2") (pintype "passive"))
      (node (ref "U$2") (pin "VBUS") (pinfunction "VBUS_VBUS") (pintype "bidirectional"))
    )
    (net (code "41") (name "Net-(IC1-CTRL)") (class "Default")
      (node (ref "C18") (pin "1") (pinfunction "1_1") (pintype "passive"))
      (node (ref "IC1") (pin "5") (pinfunction "CTRL_5") (pintype "power_in"))
    )
    (net (code "42") (name "Net-(IC2-COMP)") (class "Default")
      (node (ref "IC2") (pin "1") (pinfunction "COMP_1") (pintype "passive"))
      (node (ref "R46") (pin "2") (pinfunction "2_2") (pintype "passive"))
    )
    (net (code "43") (name "Net-(IC2-FB)") (class "Default")
      (node (ref "IC2") (pin "2") (pinfunction "FB_2") (pintype "input"))
      (node (ref "R10") (pin "2") (pinfunction "2_2") (pintype "passive"))
      (node (ref "R11") (pin "1") (pinfunction "1_1") (pintype "passive"))
    )
    (net (code "44") (name "Net-(IC3B-+IN)") (class "Default")
      (node (ref "IC3") (pin "5") (pinfunction "+IN_5") (pintype "input"))
      (node (ref "R45") (pin "2") (pinfunction "2_2") (pintype "passive"))
      (node (ref "R49") (pin "1") (pinfunction "1_1") (pintype "passive"))
    )
    (net (code "45") (name "Net-(IC3B--IN)") (class "Default")
      (node (ref "IC3") (pin "6") (pinfunction "-IN_6") (pintype "input"))
      (node (ref "R27") (pin "1") (pinfunction "1_1") (pintype "passive"))
      (node (ref "R50") (pin "2") (pinfunction "2_2") (pintype "passive"))
    )
    (net (code "46") (name "Net-(IC3B-OUT)") (class "Default")
      (node (ref "IC3") (pin "7") (pinfunction "OUT_7") (pintype "output"))
      (node (ref "T2") (pin "3") (pinfunction "G_3") (pintype "passive"))
    )
    (net (code "47") (name "Net-(LCD(5110)-Pad2)") (class "Default")
      (node (ref "LCD(5110)") (pin "2") (pinfunction "2_2") (pintype "passive"))
      (node (ref "R47") (pin "1") (pinfunction "1_1") (pintype "passive"))
    )
    (net (code "48") (name "Net-(LCD_BTN-Pad3)") (class "Default")
      (node (ref "LCD_BTN") (pin "3") (pinfunction "3_3") (pintype "passive"))
      (node (ref "LCD_BTN") (pin "4") (pinfunction "4_4") (pintype "passive"))
      (node (ref "R36") (pin "1") (pinfunction "1_1") (pintype "passive"))
      (node (ref "R38") (pin "2") (pinfunction "2_2") (pintype "passive"))
    )
    (net (code "49") (name "Net-(LCD_BTN1-Pad3)") (class "Default")
      (node (ref "LCD_BTN1") (pin "3") (pinfunction "3_3") (pintype "passive"))
      (node (ref "LCD_BTN1") (pin "4") (pinfunction "4_4") (pintype "passive"))
      (node (ref "R38") (pin "1") (pinfunction "1_1") (pintype "passive"))
      (node (ref "R39") (pin "2") (pinfunction "2_2") (pintype "passive"))
    )
    (net (code "50") (name "Net-(LCD_BTN2-Pad3)") (class "Default")
      (node (ref "LCD_BTN2") (pin "3") (pinfunction "3_3") (pintype "passive"))
      (node (ref "LCD_BTN2") (pin "4") (pinfunction "4_4") (pintype "passive"))
      (node (ref "R39") (pin "1") (pinfunction "1_1") (pintype "passive"))
    )
    (net (code "51") (name "Net-(LED4-PadA)") (class "Default")
      (node (ref "LED4") (pin "A") (pinfunction "A_A") (pintype "passive"))
      (node (ref "R16") (pin "2") (pinfunction "2_2") (pintype "passive"))
      (node (ref "R23") (pin "2") (pinfunction "2_2") (pintype "passive"))
    )
    (net (code "52") (name "Net-(PWRLED-PadA)") (class "Default")
      (node (ref "PWRLED") (pin "A") (pinfunction "A_A") (pintype "passive"))
      (node (ref "R13") (pin "1") (pinfunction "1_1") (pintype "passive"))
    )
    (net (code "53") (name "Net-(Q1-D)") (class "Default")
      (node (ref "LED4") (pin "C") (pinfunction "C_C") (pintype "passive"))
      (node (ref "Q1") (pin "3") (pinfunction "D_3") (pintype "bidirectional"))
    )
    (net (code "54") (name "Net-(Q1-G)") (class "Default")
      (node (ref "Q1") (pin "1") (pinfunction "G_1") (pintype "tri_state"))
      (node (ref "R30") (pin "2") (pinfunction "2_2") (pintype "passive"))
      (node (ref "R33") (pin "1") (pinfunction "1_1") (pintype "passive"))
    )
    (net (code "55") (name "Net-(Q2-S)") (class "Default")
      (node (ref "Q2") (pin "4") (pinfunction "S_4") (pintype "passive"))
      (node (ref "S2") (pin "3") (pinfunction "S_3") (pintype "passive"))
    )
    (net (code "56") (name "Net-(R6-Pad2)") (class "Default")
      (node (ref "R6") (pin "2") (pinfunction "2_2") (pintype "passive"))
      (node (ref "U$2") (pin "D+") (pinfunction "D+_D+") (pintype "bidirectional"))
    )
    (net (code "57") (name "Net-(R7-Pad2)") (class "Default")
      (node (ref "R7") (pin "2") (pinfunction "2_2") (pintype "passive"))
      (node (ref "U$2") (pin "D-") (pinfunction "D-_D-") (pintype "bidirectional"))
    )
    (net (code "58") (name "Net-(R14-Pad2)") (class "Default")
      (node (ref "R14") (pin "2") (pinfunction "2_2") (pintype "passive"))
      (node (ref "RXLED") (pin "A") (pinfunction "A_A") (pintype "passive"))
    )
    (net (code "59") (name "Net-(R15-Pad2)") (class "Default")
      (node (ref "R15") (pin "2") (pinfunction "2_2") (pintype "passive"))
      (node (ref "TXLED") (pin "A") (pinfunction "A_A") (pintype "passive"))
    )
    (net (code "60") (name "Net-(R17-Pad1)") (class "Default")
      (node (ref "R17") (pin "1") (pinfunction "1_1") (pintype "passive"))
      (node (ref "R18") (pin "2") (pinfunction "2_2") (pintype "passive"))
      (node (ref "T1") (pin "B") (pinfunction "B_B") (pintype "passive"))
    )
    (net (code "61") (name "Net-(R24-A)") (class "Default")
      (node (ref "R12") (pin "1") (pinfunction "1_1") (pintype "passive"))
      (node (ref "R24") (pin "3") (pinfunction "A_3") (pintype "passive"))
    )
    (net (code "62") (name "Net-(R25-A)") (class "Default")
      (node (ref "R25") (pin "3") (pinfunction "A_3") (pintype "passive"))
      (node (ref "TSALXX") (pin "K") (pinfunction "C_K") (pintype "passive"))
    )
    (net (code "63") (name "Net-(R26-Pad2)") (class "Default")
      (node (ref "R26") (pin "2") (pinfunction "2_2") (pintype "passive"))
      (node (ref "U$11") (pin "P$2") (pinfunction "P$2_P$2") (pintype "bidirectional"))
    )
    (net (code "64") (name "Net-(R28-A)") (class "Default")
      (node (ref "R28") (pin "3") (pinfunction "A_3") (pintype "passive"))
      (node (ref "TSALXX1") (pin "K") (pinfunction "C_K") (pintype "passive"))
    )
    (net (code "65") (name "Net-(R29-Pad2)") (class "Default")
      (node (ref "R29") (pin "2") (pinfunction "2_2") (pintype "passive"))
      (node (ref "U$12") (pin "P$2") (pinfunction "P$2_P$2") (pintype "bidirectional"))
    )
    (net (code "66") (name "Net-(R31-A)") (class "Default")
      (node (ref "R31") (pin "3") (pinfunction "A_3") (pintype "passive"))
      (node (ref "U$11") (pin "P$1") (pinfunction "P$1_P$1") (pintype "bidirectional"))
    )
    (net (code "67") (name "Net-(R32-Pad2)") (class "Default")
      (node (ref "R32") (pin "2") (pinfunction "2_2") (pintype "passive"))
      (node (ref "TSALXX") (pin "A") (pinfunction "A_A") (pintype "passive"))
    )
    (net (code "68") (name "Net-(R34-A)") (class "Default")
      (node (ref "R34") (pin "3") (pinfunction "A_3") (pintype "passive"))
      (node (ref "U$12") (pin "P$1") (pinfunction "P$1_P$1") (pintype "bidirectional"))
    )
    (net (code "69") (name "Net-(R35-Pad2)") (class "Default")
      (node (ref "R35") (pin "2") (pinfunction "2_2") (pintype "passive"))
      (node (ref "TSALXX1") (pin "A") (pinfunction "A_A") (pintype "passive"))
    )
    (net (code "70") (name "Net-(R40-Pad2)") (class "Default")
      (node (ref "R40") (pin "2") (pinfunction "2_2") (pintype "passive"))
      (node (ref "RXLED1") (pin "A") (pinfunction "A_A") (pintype "passive"))
    )
    (net (code "71") (name "Net-(R41-Pad2)") (class "Default")
      (node (ref "R41") (pin "2") (pinfunction "2_2") (pintype "passive"))
      (node (ref "RXLED2") (pin "A") (pinfunction "A_A") (pintype "passive"))
    )
    (net (code "72") (name "Net-(R42-Pad2)") (class "Default")
      (node (ref "R42") (pin "2") (pinfunction "2_2") (pintype "passive"))
      (node (ref "RXLED3") (pin "A") (pinfunction "A_A") (pintype "passive"))
    )
    (net (code "73") (name "Net-(R43-Pad2)") (class "Default")
      (node (ref "R43") (pin "2") (pinfunction "2_2") (pintype "passive"))
      (node (ref "RXLED4") (pin "A") (pinfunction "A_A") (pintype "passive"))
    )
    (net (code "74") (name "Net-(S1-O)") (class "Default")
      (node (ref "R30") (pin "1") (pinfunction "1_1") (pintype "passive"))
      (node (ref "S1") (pin "1") (pinfunction "O_1") (pintype "passive"))
    )
    (net (code "75") (name "Net-(S2-O)") (class "Default")
      (node (ref "S2") (pin "1") (pinfunction "O_1") (pintype "passive"))
      (node (ref "S2") (pin "2") (pinfunction "P_2") (pintype "passive"))
      (node (ref "S3") (pin "2") (pinfunction "P_2") (pintype "passive"))
    )
    (net (code "76") (name "Net-(S4-O)") (class "Default")
      (node (ref "S4") (pin "1") (pinfunction "O_1") (pintype "passive"))
      (node (ref "S4") (pin "2") (pinfunction "P_2") (pintype "passive"))
      (node (ref "U$4") (pin "3") (pinfunction "D_3") (pintype "passive"))
    )
    (net (code "77") (name "Net-(SG1-Pad-)") (class "Default")
      (node (ref "SG1") (pin "-") (pinfunction "-_-") (pintype "passive"))
      (node (ref "T1") (pin "C") (pinfunction "C_C") (pintype "passive"))
    )
    (net (code "78") (name "Net-(U$1-AREF)") (class "Default")
      (node (ref "C1") (pin "1") (pinfunction "1_1") (pintype "passive"))
      (node (ref "U$1") (pin "42") (pinfunction "AREF_42") (pintype "bidirectional"))
    )
    (net (code "79") (name "Net-(U$1-PE2{slash}~{HWB})") (class "Default")
      (node (ref "R3") (pin "1") (pinfunction "1_1") (pintype "passive"))
      (node (ref "U$1") (pin "33") (pinfunction "PE2/~{HWB}_33") (pintype "bidirectional"))
    )
    (net (code "80") (name "Net-(U$1-UCAP)") (class "Default")
      (node (ref "C6") (pin "2") (pinfunction "2_2") (pintype "passive"))
      (node (ref "U$1") (pin "6") (pinfunction "UCAP_6") (pintype "bidirectional"))
    )
    (net (code "81") (name "Net-(U$1-XTAL2)") (class "Default")
      (node (ref "C3") (pin "2") (pinfunction "2_2") (pintype "passive"))
      (node (ref "CRYSTAL") (pin "1") (pinfunction "1_1") (pintype "passive"))
      (node (ref "R1") (pin "1") (pinfunction "1_1") (pintype "passive"))
      (node (ref "U$1") (pin "16") (pinfunction "XTAL2_16") (pintype "bidirectional"))
    )
    (net (code "82") (name "Net-(U$4-G)") (class "Default")
      (node (ref "R48") (pin "2") (pinfunction "2_2") (pintype "passive"))
      (node (ref "U$4") (pin "1") (pinfunction "G_1") (pintype "passive"))
    )
    (net (code "83") (name "RESET") (class "Default")
      (node (ref "D1") (pin "A") (pinfunction "A_A") (pintype "passive"))
      (node (ref "J1") (pin "5") (pinfunction "5_5") (pintype "passive"))
      (node (ref "R2") (pin "1") (pinfunction "1_1") (pintype "passive"))
      (node (ref "RESET_BUTTON") (pin "1") (pinfunction "1_1") (pintype "passive"))
      (node (ref "RESET_BUTTON") (pin "2") (pinfunction "2_2") (pintype "passive"))
      (node (ref "U$1") (pin "13") (pinfunction "~{RESET}_13") (pintype "bidirectional"))
    )
    (net (code "84") (name "RXLED") (class "Default")
      (node (ref "LCD(5110)") (pin "6") (pinfunction "6_6") (pintype "passive"))
      (node (ref "RXLED") (pin "C") (pinfunction "C_C") (pintype "passive"))
      (node (ref "U$1") (pin "8") (pinfunction "PB0(SS)_8") (pintype "bidirectional"))
    )
    (net (code "85") (name "SCK") (class "Default")
      (node (ref "J1") (pin "3") (pinfunction "3_3") (pintype "passive"))
      (node (ref "LCD(5110)") (pin "4") (pinfunction "4_4") (pintype "passive"))
      (node (ref "U$1") (pin "9") (pinfunction "PB1(SCK)_9") (pintype "bidirectional"))
    )
    (net (code "86") (name "SCL") (class "Default")
      (node (ref "I2C") (pin "3") (pinfunction "3_3") (pintype "passive"))
      (node (ref "R4") (pin "1") (pinfunction "1_1") (pintype "passive"))
      (node (ref "U$1") (pin "18") (pinfunction "PD0(SCL)_18") (pintype "bidirectional"))
    )
    (net (code "87") (name "SDA") (class "Default")
      (node (ref "I2C") (pin "4") (pinfunction "4_4") (pintype "passive"))
      (node (ref "R5") (pin "1") (pinfunction "1_1") (pintype "passive"))
      (node (ref "U$1") (pin "19") (pinfunction "PD1(SDA)_19") (pintype "bidirectional"))
    )
    (net (code "88") (name "TXLED") (class "Default")
      (node (ref "TXLED") (pin "C") (pinfunction "C_C") (pintype "passive"))
      (node (ref "U$1") (pin "22") (pinfunction "PD5_22") (pintype "bidirectional"))
    )
    (net (code "89") (name "VIN") (class "Default")
      (node (ref "C10") (pin "+") (pinfunction "+_+") (pintype "passive"))
      (node (ref "C21") (pin "1") (pinfunction "1_1") (pintype "passive"))
      (node (ref "IC2") (pin "5") (pinfunction "VIN_5") (pintype "power_in"))
      (node (ref "L2") (pin "1") (pinfunction "1_1") (pintype "passive"))
      (node (ref "S3") (pin "1") (pinfunction "O_1") (pintype "passive"))
    )
    (net (code "90") (name "VS1") (class "Default")
      (node (ref "C23") (pin "1") (pinfunction "1_1") (pintype "passive"))
      (node (ref "R19") (pin "1") (pinfunction "1_1") (pintype "passive"))
      (node (ref "U$9") (pin "VS") (pinfunction "VS_VS") (pintype "bidirectional"))
    )
    (net (code "91") (name "VS2") (class "Default")
      (node (ref "C24") (pin "1") (pinfunction "1_1") (pintype "passive"))
      (node (ref "R20") (pin "1") (pinfunction "1_1") (pintype "passive"))
      (node (ref "U$8") (pin "VS") (pinfunction "VS_VS") (pintype "bidirectional"))
    )
    (net (code "92") (name "VS3") (class "Default")
      (node (ref "C25") (pin "1") (pinfunction "1_1") (pintype "passive"))
      (node (ref "R21") (pin "1") (pinfunction "1_1") (pintype "passive"))
      (node (ref "U$6") (pin "2") (pinfunction "VS_2") (pintype "bidirectional"))
    )
    (net (code "93") (name "VS4") (class "Default")
      (node (ref "C26") (pin "1") (pinfunction "1_1") (pintype "passive"))
      (node (ref "R22") (pin "1") (pinfunction "1_1") (pintype "passive"))
      (node (ref "U$7") (pin "2") (pinfunction "VS_2") (pintype "bidirectional"))
    )
    (net (code "94") (name "VUSB") (class "Default")
      (node (ref "C8") (pin "1") (pinfunction "1_1") (pintype "passive"))
      (node (ref "C9") (pin "1") (pinfunction "1_1") (pintype "passive"))
      (node (ref "F1") (pin "1") (pinfunction "1_1") (pintype "passive"))
      (node (ref "T2") (pin "1") (pinfunction "D_1") (pintype "passive"))
      (node (ref "U$1") (pin "7") (pinfunction "VBUS_7") (pintype "bidirectional"))
    )
    (net (code "95") (name "V_BATT") (class "Default")
      (node (ref "C12") (pin "+") (pinfunction "+_+") (pintype "passive"))
      (node (ref "C13") (pin "1") (pinfunction "1_1") (pintype "passive"))
      (node (ref "C14") (pin "1") (pinfunction "1_1") (pintype "passive"))
      (node (ref "C16") (pin "1") (pinfunction "1_1") (pintype "passive"))
      (node (ref "C22") (pin "1") (pinfunction "1_1") (pintype "passive"))
      (node (ref "D2") (pin "1") (pinfunction "C_1") (pintype "passive"))
      (node (ref "R10") (pin "1") (pinfunction "1_1") (pintype "passive"))
      (node (ref "R49") (pin "2") (pinfunction "2_2") (pintype "passive"))
      (node (ref "S3") (pin "3") (pinfunction "S_3") (pintype "passive"))
      (node (ref "U$5") (pin "3") (pinfunction "VIN_3") (pintype "bidirectional"))
      (node (ref "U1") (pin "13") (pinfunction "VM2_13") (pintype "bidirectional"))
      (node (ref "U1") (pin "14") (pinfunction "VM3_14") (pintype "bidirectional"))
      (node (ref "U1") (pin "24") (pinfunction "VM1_24") (pintype "bidirectional"))
    )
    (net (code "96") (name "unconnected-(IC1-DIS-Pad7)") (class "Default")
      (node (ref "IC1") (pin "7") (pinfunction "DIS_7") (pintype "input"))
    )
    (net (code "97") (name "unconnected-(R24-E-Pad1)") (class "Default")
      (node (ref "R24") (pin "1") (pinfunction "E_1") (pintype "passive"))
    )
    (net (code "98") (name "unconnected-(R25-E-Pad1)") (class "Default")
      (node (ref "R25") (pin "1") (pinfunction "E_1") (pintype "passive"))
    )
    (net (code "99") (name "unconnected-(R28-E-Pad1)") (class "Default")
      (node (ref "R28") (pin "1") (pinfunction "E_1") (pintype "passive"))
    )
    (net (code "100") (name "unconnected-(R31-E-Pad1)") (class "Default")
      (node (ref "R31") (pin "1") (pinfunction "E_1") (pintype "passive"))
    )
    (net (code "101") (name "unconnected-(R34-E-Pad1)") (class "Default")
      (node (ref "R34") (pin "1") (pinfunction "E_1") (pintype "passive"))
    )
  )
)
